# tps61040.net
KiCad netlist of a schematic drawn in EAGLE
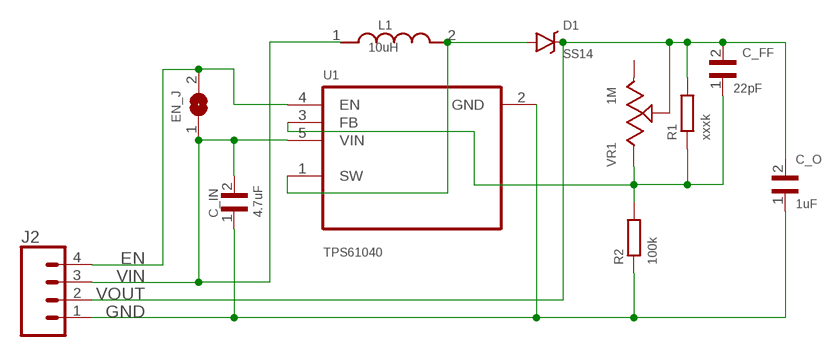
[diagram p0: schematic, sheet 1]

(export (version "E")
  (design (tool "Eeschema 10.0.6"))
  (components
    (comp (ref "C_FF")
      (value "22pF")
      (footprint "eagle-import:WCAP-CSGP_0603_REFLOW")
      (libsource (lib "eagle-import") (part "WCAP-CSGP_0603-REFLOW"))
    )
    (comp (ref "C_IN")
      (value "4.7uF")
      (footprint "eagle-import:WCAP-CSGP_0603_REFLOW")
      (libsource (lib "eagle-import") (part "WCAP-CSGP_0603-REFLOW"))
    )
    (comp (ref "C_O")
      (value "1uF")
      (footprint "eagle-import:WCAP-CSGP_0603_REFLOW")
      (libsource (lib "eagle-import") (part "WCAP-CSGP_0603-REFLOW"))
    )
    (comp (ref "D1")
      (value "SS14")
      (footprint "eagle-import:DO-214AC")
      (fields (field (name "MF") "MDD") (field (name "MP") "SS54"))
      (libsource (lib "eagle-import") (part "SS54"))
    )
    (comp (ref "EN_J")
      (value "SJ")
      (footprint "eagle-import:SJ")
      (libsource (lib "eagle-import") (part "SJ"))
    )
    (comp (ref "J2")
      (value "CONN_041X04_NO_SILK")
      (footprint "eagle-import:1X04_NO_SILK")
      (libsource (lib "eagle-import") (part "CONN_041X04_NO_SILK"))
    )
    (comp (ref "L1")
      (value "10uH")
      (footprint "eagle-import:CD43")
      (libsource (lib "eagle-import") (part "CD43"))
    )
    (comp (ref "R1")
      (value "xxxk")
      (footprint "eagle-import:R0603")
      (libsource (lib "eagle-import") (part "R-EU_R0603"))
    )
    (comp (ref "R2")
      (value "100k")
      (footprint "eagle-import:R0603")
      (libsource (lib "eagle-import") (part "R-EU_R0603"))
    )
    (comp (ref "U1")
      (value "TPS61040")
      (footprint "eagle-import:SOT95P280X145-5N")
      (fields (field (name "MF") "Texas Instruments") (field (name "MP") "TPS61040DBVR"))
      (libsource (lib "eagle-import") (part "TPS61040DBVR"))
    )
    (comp (ref "VR1")
      (value "1M")
      (footprint "eagle-import:TRIMMER_TC33X-2-103G")
      (fields (field (name "MF") "Bourns") (field (name "MP") "TC33X-2-103G"))
      (libsource (lib "eagle-import") (part "TC33X-2-103G"))
    )
  )
  (nets
    (net (code "1") (name "/EN") (class "Default")
      (node (ref "EN_J") (pin "2") (pinfunction "2_2") (pintype "passive"))
      (node (ref "J2") (pin "4") (pinfunction "4_4") (pintype "passive"))
      (node (ref "U1") (pin "4") (pinfunction "EN_4") (pintype "input"))
    )
    (net (code "2") (name "/GND") (class "Default")
      (node (ref "C_IN") (pin "1") (pinfunction "1_1") (pintype "passive"))
      (node (ref "C_O") (pin "1") (pinfunction "1_1") (pintype "passive"))
      (node (ref "J2") (pin "1") (pinfunction "1_1") (pintype "passive"))
      (node (ref "R2") (pin "1") (pinfunction "1_1") (pintype "passive"))
      (node (ref "U1") (pin "2") (pinfunction "GND_2") (pintype "power_in"))
    )
    (net (code "3") (name "/VIN") (class "Default")
      (node (ref "C_IN") (pin "2") (pinfunction "2_2") (pintype "passive"))
      (node (ref "EN_J") (pin "1") (pinfunction "1_1") (pintype "passive"))
      (node (ref "J2") (pin "3") (pinfunction "3_3") (pintype "passive"))
      (node (ref "L1") (pin "1") (pinfunction "1_1") (pintype "bidirectional"))
      (node (ref "U1") (pin "5") (pinfunction "VIN_5") (pintype "input"))
    )
    (net (code "4") (name "/VOUT") (class "Default")
      (node (ref "C_FF") (pin "2") (pinfunction "2_2") (pintype "passive"))
      (node (ref "C_O") (pin "2") (pinfunction "2_2") (pintype "passive"))
      (node (ref "D1") (pin "C") (pinfunction "C_C") (pintype "passive"))
      (node (ref "J2") (pin "2") (pinfunction "2_2") (pintype "passive"))
      (node (ref "R1") (pin "2") (pinfunction "2_2") (pintype "passive"))
      (node (ref "VR1") (pin "2") (pinfunction "WIPER_2") (pintype "passive"))
    )
    (net (code "5") (name "Net-(U1-FB)") (class "Default")
      (node (ref "C_FF") (pin "1") (pinfunction "1_1") (pintype "passive"))
      (node (ref "R1") (pin "1") (pinfunction "1_1") (pintype "passive"))
      (node (ref "R2") (pin "2") (pinfunction "2_2") (pintype "passive"))
      (node (ref "U1") (pin "3") (pinfunction "FB_3") (pintype "input"))
      (node (ref "VR1") (pin "1") (pinfunction "CCW_1") (pintype "passive"))
    )
    (net (code "6") (name "Net-(U1-SW)") (class "Default")
      (node (ref "D1") (pin "A") (pinfunction "A_A") (pintype "passive"))
      (node (ref "L1") (pin "2") (pinfunction "2_2") (pintype "bidirectional"))
      (node (ref "U1") (pin "1") (pinfunction "SW_1") (pintype "bidirectional"))
    )
    (net (code "7") (name "unconnected-(VR1-CW-Pad3)") (class "Default")
      (node (ref "VR1") (pin "3") (pinfunction "CW_3") (pintype "passive"))
    )
  )
)
